# Test_board.net
KiCad netlist of a schematic drawn in EAGLE
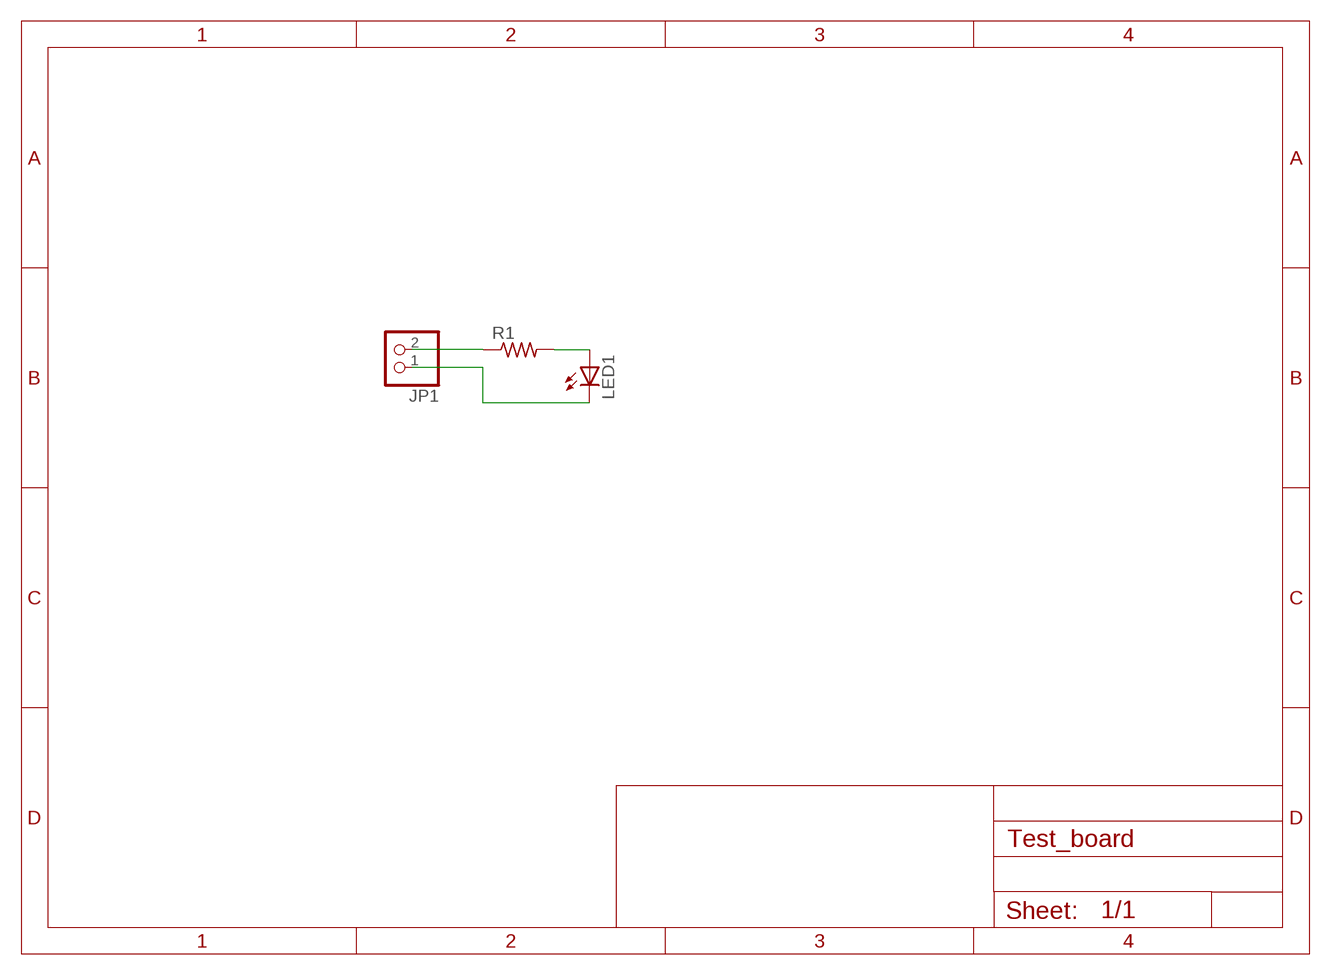
[diagram p0: schematic, sheet 1]

(export (version "E")
  (design (tool "Eeschema 10.0.6"))
  (components
    (comp (ref "JP1")
      (value "PINHD-1X2")
      (footprint "eagle-import:1X02")
      (libsource (lib "eagle-import") (part "PINHD-1X2"))
    )
    (comp (ref "LED1")
      (value "LEDSML1206")
      (footprint "eagle-import:SML1206")
      (libsource (lib "eagle-import") (part "LEDSML1206"))
    )
    (comp (ref "R1")
      (value "R-US_M1206")
      (footprint "eagle-import:M1206")
      (libsource (lib "eagle-import") (part "R-US_M1206"))
    )
  )
  (nets
    (net (code "1") (name "Net-(JP1-Pad1)") (class "Default")
      (node (ref "JP1") (pin "1") (pinfunction "1_1") (pintype "passive"))
      (node (ref "LED1") (pin "C") (pinfunction "C_C") (pintype "passive"))
    )
    (net (code "2") (name "Net-(JP1-Pad2)") (class "Default")
      (node (ref "JP1") (pin "2") (pinfunction "2_2") (pintype "passive"))
      (node (ref "R1") (pin "1") (pinfunction "1_1") (pintype "passive"))
    )
    (net (code "3") (name "Net-(LED1-PadA)") (class "Default")
      (node (ref "LED1") (pin "A") (pinfunction "A_A") (pintype "passive"))
      (node (ref "R1") (pin "2") (pinfunction "2_2") (pintype "passive"))
    )
  )
)
